# Sheet1.net
KiCad netlist of a schematic drawn in Altium Designer
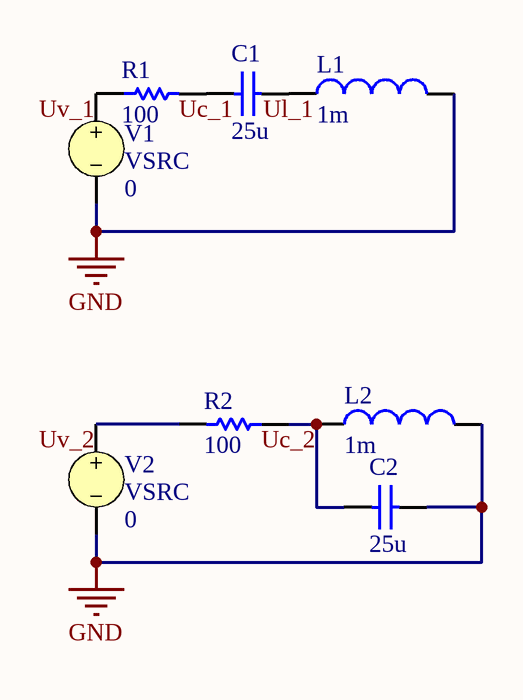
[diagram p0: Sheet1.SchDoc]

(export (version "E")
  (design (tool "Eeschema 10.0.6"))
  (components
    (comp (ref "C1")
      (value "25u")
      (description "Capacitor")
      (libsource (lib "Simulation Generic Components") (part "Capacitor"))
    )
    (comp (ref "C2")
      (value "25u")
      (description "Capacitor")
      (libsource (lib "Simulation Generic Components") (part "Capacitor"))
    )
    (comp (ref "L1")
      (value "1m")
      (description "Inductor")
      (libsource (lib "Simulation Generic Components") (part "Inductor"))
    )
    (comp (ref "L2")
      (value "1m")
      (description "Inductor")
      (libsource (lib "Simulation Generic Components") (part "Inductor"))
    )
    (comp (ref "R1")
      (value "100")
      (description "Resistor")
      (libsource (lib "Simulation Generic Components") (part "Resistor"))
    )
    (comp (ref "R2")
      (value "100")
      (description "Resistor")
      (libsource (lib "Simulation Generic Components") (part "Resistor"))
    )
    (comp (ref "V1")
      (value "VSRC")
      (description "Voltage Source")
      (fields (field (name "DC MAGNITUDE") "0") (field (name "PUBLISHER") "Altium Limited"))
      (libsource (lib "Simulation Generic Components") (part "VSRC"))
    )
    (comp (ref "V2")
      (value "VSRC")
      (description "Voltage Source")
      (fields (field (name "DC MAGNITUDE") "0") (field (name "PUBLISHER") "Altium Limited"))
      (libsource (lib "Simulation Generic Components") (part "VSRC"))
    )
  )
  (nets
    (net (code "1") (name "/Uc_1") (class "Default")
      (node (ref "C1") (pin "2") (pinfunction "2_2") (pintype "passive"))
      (node (ref "R1") (pin "2") (pinfunction "2_2") (pintype "passive"))
    )
    (net (code "2") (name "/Uc_2") (class "Default")
      (node (ref "C2") (pin "1") (pinfunction "1_1") (pintype "passive"))
      (node (ref "L2") (pin "1") (pinfunction "1_1") (pintype "passive"))
      (node (ref "R2") (pin "1") (pinfunction "1_1") (pintype "passive"))
    )
    (net (code "3") (name "/Ul_1") (class "Default")
      (node (ref "C1") (pin "1") (pinfunction "1_1") (pintype "passive"))
      (node (ref "L1") (pin "1") (pinfunction "1_1") (pintype "passive"))
    )
    (net (code "4") (name "/Uv_1") (class "Default")
      (node (ref "R1") (pin "1") (pinfunction "1_1") (pintype "passive"))
      (node (ref "V1") (pin "1") (pinfunction "1_1") (pintype "passive"))
    )
    (net (code "5") (name "/Uv_2") (class "Default")
      (node (ref "R2") (pin "2") (pinfunction "2_2") (pintype "passive"))
      (node (ref "V2") (pin "1") (pinfunction "1_1") (pintype "passive"))
    )
    (net (code "6") (name "GND") (class "Default")
      (node (ref "C2") (pin "2") (pinfunction "2_2") (pintype "passive"))
      (node (ref "L1") (pin "2") (pinfunction "2_2") (pintype "passive"))
      (node (ref "L2") (pin "2") (pinfunction "2_2") (pintype "passive"))
      (node (ref "V1") (pin "2") (pinfunction "2_2") (pintype "passive"))
      (node (ref "V2") (pin "2") (pinfunction "2_2") (pintype "passive"))
    )
  )
)
